# MIXR_Input_-_ADC_Power_Communication.net
KiCad netlist of a schematic drawn in Altium Designer
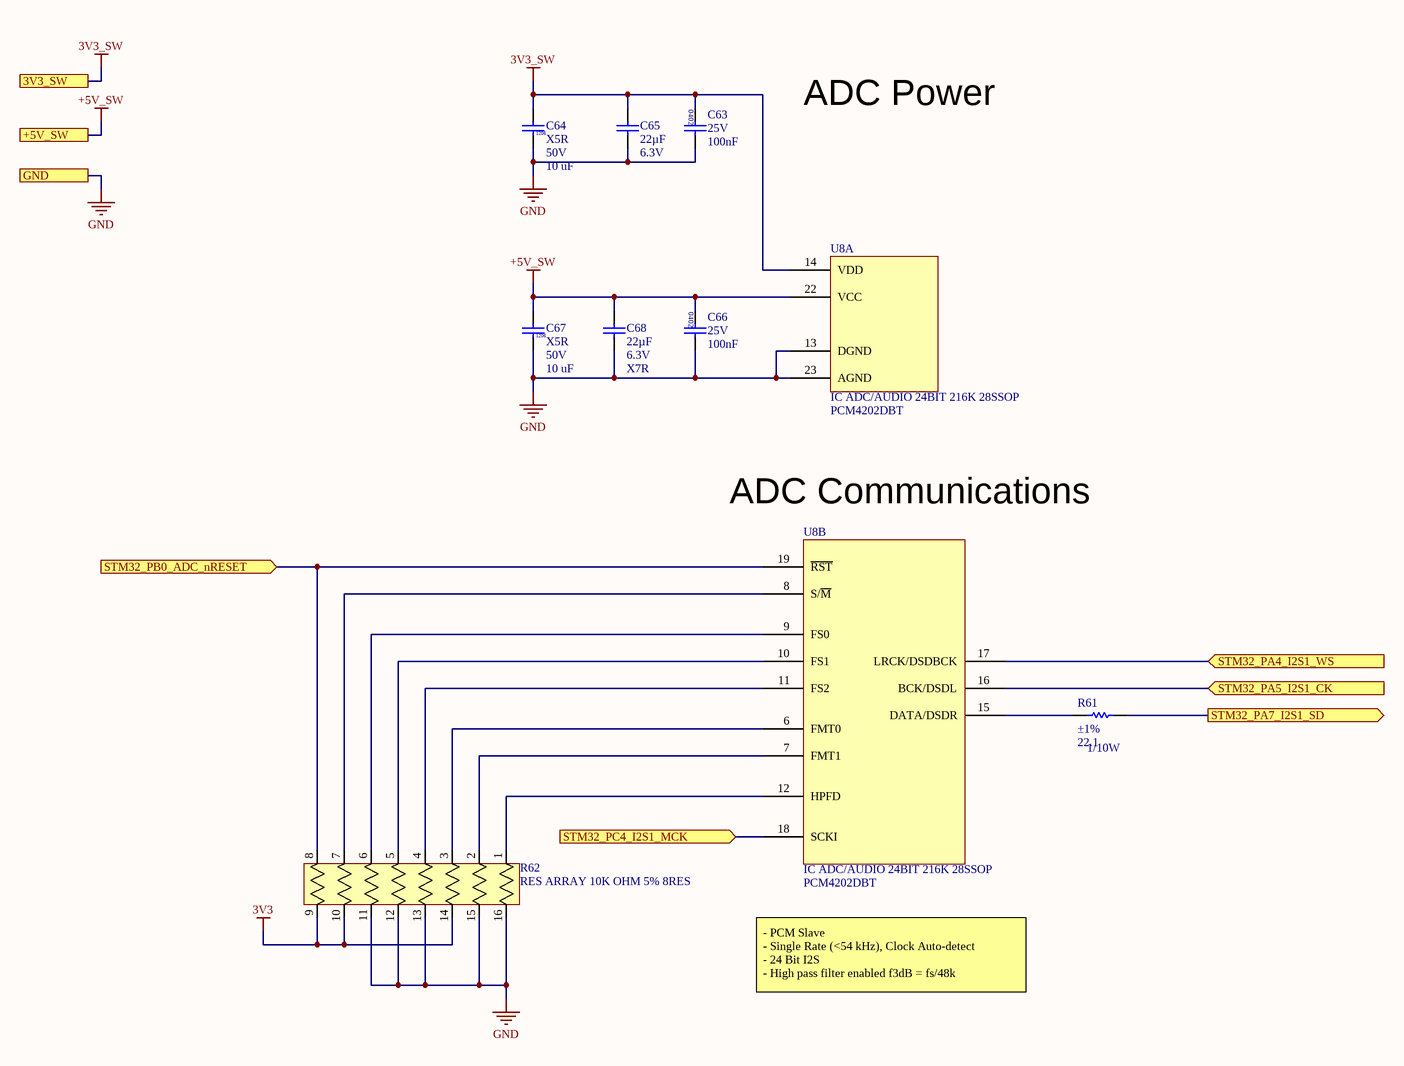
[diagram p0: MIXR Input - ADC Power & Communication.SchDoc]

(export (version "E")
  (design (tool "Eeschema 10.0.6"))
  (components
    (comp (ref "C63")
      (value "CAP CER 0.1UF 16V X7R 0402")
      (footprint "CAP 0402")
      (description "Cap Ceramic 0.1uF 25V X7R 10% SMD 0402 125C Paper T/R")
      (fields
        (field (name "MANUFACTURER") "Murata")
        (field (name "MANUFACTURER PART NUMBER") "GRM155R71E104KE14D")
        (field (name "VOLTAGE") "25V")
        (field (name "CAPACITANCE") "100nF")
      )
      (libsource (lib "Schematic Diagrams") (part "CAP CER 0.1UF 16V X7R 0402"))
    )
    (comp (ref "C64")
      (value "CAP CER 10uF 50V 20% X5R 1206")
      (footprint "CAP, 1206")
      (description "10µF ±20% 50V Ceramic Capacitor X5R 1206 (3216 Metric)")
      (fields
        (field (name "MANUFACTURER") "Murata")
        (field (name "TOLERANCE") "20%")
        (field (name "RATING") "X5R")
        (field (name "VOLTAGE RATING") "50V")
        (field (name "CAPACITANCE") "10 uF")
      )
      (libsource (lib "Schematic Diagrams") (part "CAP CER 10uF 50V 20% X5R 1206"))
    )
    (comp (ref "C65")
      (value "CAP CER 22UF 6.3V ±10% X7R 1206")
      (footprint "CAP, 1206")
      (description "22µF ±10% 6.3V Ceramic Capacitor X7R 1206 (3216 Metric)")
      (fields
        (field (name "TOLERANCE") "±10%")
        (field (name "CAPACITANCE") "22µF")
        (field (name "VOLTAGE") "6.3V")
      )
      (libsource (lib "Schematic Diagrams") (part "CAP CER 22UF 6.3V ±10% X7R 1206"))
    )
    (comp (ref "C66")
      (value "CAP CER 0.1UF 16V X7R 0402")
      (footprint "CAP 0402")
      (description "Cap Ceramic 0.1uF 25V X7R 10% SMD 0402 125C Paper T/R")
      (fields
        (field (name "MANUFACTURER") "Murata")
        (field (name "MANUFACTURER PART NUMBER") "GRM155R71E104KE14D")
        (field (name "VOLTAGE") "25V")
        (field (name "CAPACITANCE") "100nF")
      )
      (libsource (lib "Schematic Diagrams") (part "CAP CER 0.1UF 16V X7R 0402"))
    )
    (comp (ref "C67")
      (value "CAP CER 10uF 50V 20% X5R 1206")
      (footprint "CAP, 1206")
      (description "10µF ±20% 50V Ceramic Capacitor X5R 1206 (3216 Metric)")
      (fields
        (field (name "MANUFACTURER") "Murata")
        (field (name "TOLERANCE") "20%")
        (field (name "RATING") "X5R")
        (field (name "VOLTAGE RATING") "50V")
        (field (name "CAPACITANCE") "10 uF")
      )
      (libsource (lib "Schematic Diagrams") (part "CAP CER 10uF 50V 20% X5R 1206"))
    )
    (comp (ref "C68")
      (value "CAP CER 22UF 6.3V ±10% X7R 1206")
      (footprint "CAP, 1206")
      (description "22µF ±10% 6.3V Ceramic Capacitor X7R 1206 (3216 Metric)")
      (fields
        (field (name "TOLERANCE") "±10%")
        (field (name "CAPACITANCE") "22µF")
        (field (name "VOLTAGE") "6.3V")
        (field (name "TEMPERATURE COEFFICIENT") "X7R")
      )
      (libsource (lib "Schematic Diagrams") (part "CAP CER 22UF 6.3V ±10% X7R 1206"))
    )
    (comp (ref "R61")
      (value "RES 22.1 OHM 1% 1/10W 0603")
      (footprint "RES, 0603")
      (description "22.1 Ohm ±1% 0.1W, 1/10W Chip Resistor 0603 (1608 Metric) Moisture Resistant Thick Film")
      (fields
        (field (name "TOLERANCE") "±1%")
        (field (name "RESISTANCE") "22.1")
        (field (name "POWER") "1/10W")
      )
      (libsource (lib "Schematic Diagrams") (part "RES 22.1 OHM 1% 1/10W 0603"))
    )
    (comp (ref "R62")
      (value "RES ARRAY 10K OHM 5% 8RES")
      (footprint "RES ARRAY, 8 POS 1506")
      (description "RES ARRAY SMD 10K 5% 62.5mW 1506")
      (fields
        (field (name "MANUFACTURER_PART_NUMBER") "EXB-2HV103JV")
        (field (name "MANUFACTURER") "Panasonic Electronic Components")
        (field (name "COPYRIGHT") "Copyright (C) 2015 Accelerated Designs. All rights reserved")
      )
      (libsource (lib "Schematic Diagrams") (part "RES ARRAY 10K OHM 5% 8RES EXB-2HV103JV"))
    )
    (comp (ref "U8")
      (value "IC ADC/AUDIO 24BIT 216K 28SSOP")
      (footprint "IC ADC 24 BIT AUDIO 216 KHZ SSOP-28")
      (description "ADC, Audio 24 bit 216k DSP, PCM 28-SSOP")
      (fields
        (field (name "MANUFACTURER") "Texas Instruments")
        (field (name "MANUFACTURER PART NUMBER") "PCM4202DBT")
      )
      (libsource (lib "Schematic Diagrams") (part "IC ADC 24 BIT AUDIO 216KHZ SSOP-28"))
    )
  )
  (nets
    (net (code "1") (name "+5V_SW") (class "Default")
      (node (ref "C66") (pin "1") (pinfunction "1_1") (pintype "passive"))
      (node (ref "C67") (pin "1") (pinfunction "1_1") (pintype "passive"))
      (node (ref "C68") (pin "1") (pinfunction "1_1") (pintype "passive"))
      (node (ref "U8") (pin "22") (pinfunction "VCC_22") (pintype "passive"))
    )
    (net (code "2") (name "/STM32_PA4_I2S1_WS") (class "Default")
      (node (ref "U8") (pin "17") (pinfunction "LRCK/DSDBCK_17") (pintype "passive"))
    )
    (net (code "3") (name "/STM32_PA5_I2S1_CK") (class "Default")
      (node (ref "U8") (pin "16") (pinfunction "BCK/DSDL_16") (pintype "passive"))
    )
    (net (code "4") (name "/STM32_PA7_I2S1_SD") (class "Default")
      (node (ref "R61") (pin "2") (pinfunction "2_2") (pintype "passive"))
    )
    (net (code "5") (name "/STM32_PB0_ADC_nRESET") (class "Default")
      (node (ref "R62") (pin "8") (pinfunction "8_8") (pintype "passive"))
      (node (ref "U8") (pin "19") (pinfunction "~{RST}_19") (pintype "passive"))
    )
    (net (code "6") (name "/STM32_PC4_I2S1_MCK") (class "Default")
      (node (ref "U8") (pin "18") (pinfunction "SCKI_18") (pintype "passive"))
    )
    (net (code "7") (name "3V3") (class "Default")
      (node (ref "R62") (pin "10") (pinfunction "10_10") (pintype "passive"))
      (node (ref "R62") (pin "14") (pinfunction "14_14") (pintype "passive"))
      (node (ref "R62") (pin "9") (pinfunction "9_9") (pintype "passive"))
    )
    (net (code "8") (name "3V3_SW") (class "Default")
      (node (ref "C63") (pin "1") (pinfunction "1_1") (pintype "passive"))
      (node (ref "C64") (pin "1") (pinfunction "1_1") (pintype "passive"))
      (node (ref "C65") (pin "1") (pinfunction "1_1") (pintype "passive"))
      (node (ref "U8") (pin "14") (pinfunction "VDD_14") (pintype "passive"))
    )
    (net (code "9") (name "GND") (class "Default")
      (node (ref "C63") (pin "2") (pinfunction "2_2") (pintype "passive"))
      (node (ref "C64") (pin "2") (pinfunction "2_2") (pintype "passive"))
      (node (ref "C65") (pin "2") (pinfunction "2_2") (pintype "passive"))
      (node (ref "C66") (pin "2") (pinfunction "2_2") (pintype "passive"))
      (node (ref "C67") (pin "2") (pinfunction "2_2") (pintype "passive"))
      (node (ref "C68") (pin "2") (pinfunction "2_2") (pintype "passive"))
      (node (ref "R62") (pin "11") (pinfunction "11_11") (pintype "passive"))
      (node (ref "R62") (pin "12") (pinfunction "12_12") (pintype "passive"))
      (node (ref "R62") (pin "13") (pinfunction "13_13") (pintype "passive"))
      (node (ref "R62") (pin "15") (pinfunction "15_15") (pintype "passive"))
      (node (ref "R62") (pin "16") (pinfunction "16_16") (pintype "passive"))
      (node (ref "U8") (pin "13") (pinfunction "DGND_13") (pintype "passive"))
      (node (ref "U8") (pin "23") (pinfunction "AGND_23") (pintype "passive"))
    )
    (net (code "10") (name "Net-(U8B-DATA{slash}DSDR)") (class "Default")
      (node (ref "R61") (pin "1") (pinfunction "1_1") (pintype "passive"))
      (node (ref "U8") (pin "15") (pinfunction "DATA/DSDR_15") (pintype "passive"))
    )
    (net (code "11") (name "Net-(U8B-FMT0)") (class "Default")
      (node (ref "R62") (pin "3") (pinfunction "3_3") (pintype "passive"))
      (node (ref "U8") (pin "6") (pinfunction "FMT0_6") (pintype "passive"))
    )
    (net (code "12") (name "Net-(U8B-FMT1)") (class "Default")
      (node (ref "R62") (pin "2") (pinfunction "2_2") (pintype "passive"))
      (node (ref "U8") (pin "7") (pinfunction "FMT1_7") (pintype "passive"))
    )
    (net (code "13") (name "Net-(U8B-FS0)") (class "Default")
      (node (ref "R62") (pin "6") (pinfunction "6_6") (pintype "passive"))
      (node (ref "U8") (pin "9") (pinfunction "FS0_9") (pintype "passive"))
    )
    (net (code "14") (name "Net-(U8B-FS1)") (class "Default")
      (node (ref "R62") (pin "5") (pinfunction "5_5") (pintype "passive"))
      (node (ref "U8") (pin "10") (pinfunction "FS1_10") (pintype "passive"))
    )
    (net (code "15") (name "Net-(U8B-FS2)") (class "Default")
      (node (ref "R62") (pin "4") (pinfunction "4_4") (pintype "passive"))
      (node (ref "U8") (pin "11") (pinfunction "FS2_11") (pintype "passive"))
    )
    (net (code "16") (name "Net-(U8B-HPFD)") (class "Default")
      (node (ref "R62") (pin "1") (pinfunction "1_1") (pintype "passive"))
      (node (ref "U8") (pin "12") (pinfunction "HPFD_12") (pintype "passive"))
    )
    (net (code "17") (name "Net-(U8B-S{slash}~{M})") (class "Default")
      (node (ref "R62") (pin "7") (pinfunction "7_7") (pintype "passive"))
      (node (ref "U8") (pin "8") (pinfunction "S/~{M}_8") (pintype "passive"))
    )
  )
)
